# Storage.net
KiCad netlist of a schematic drawn in Altium Designer
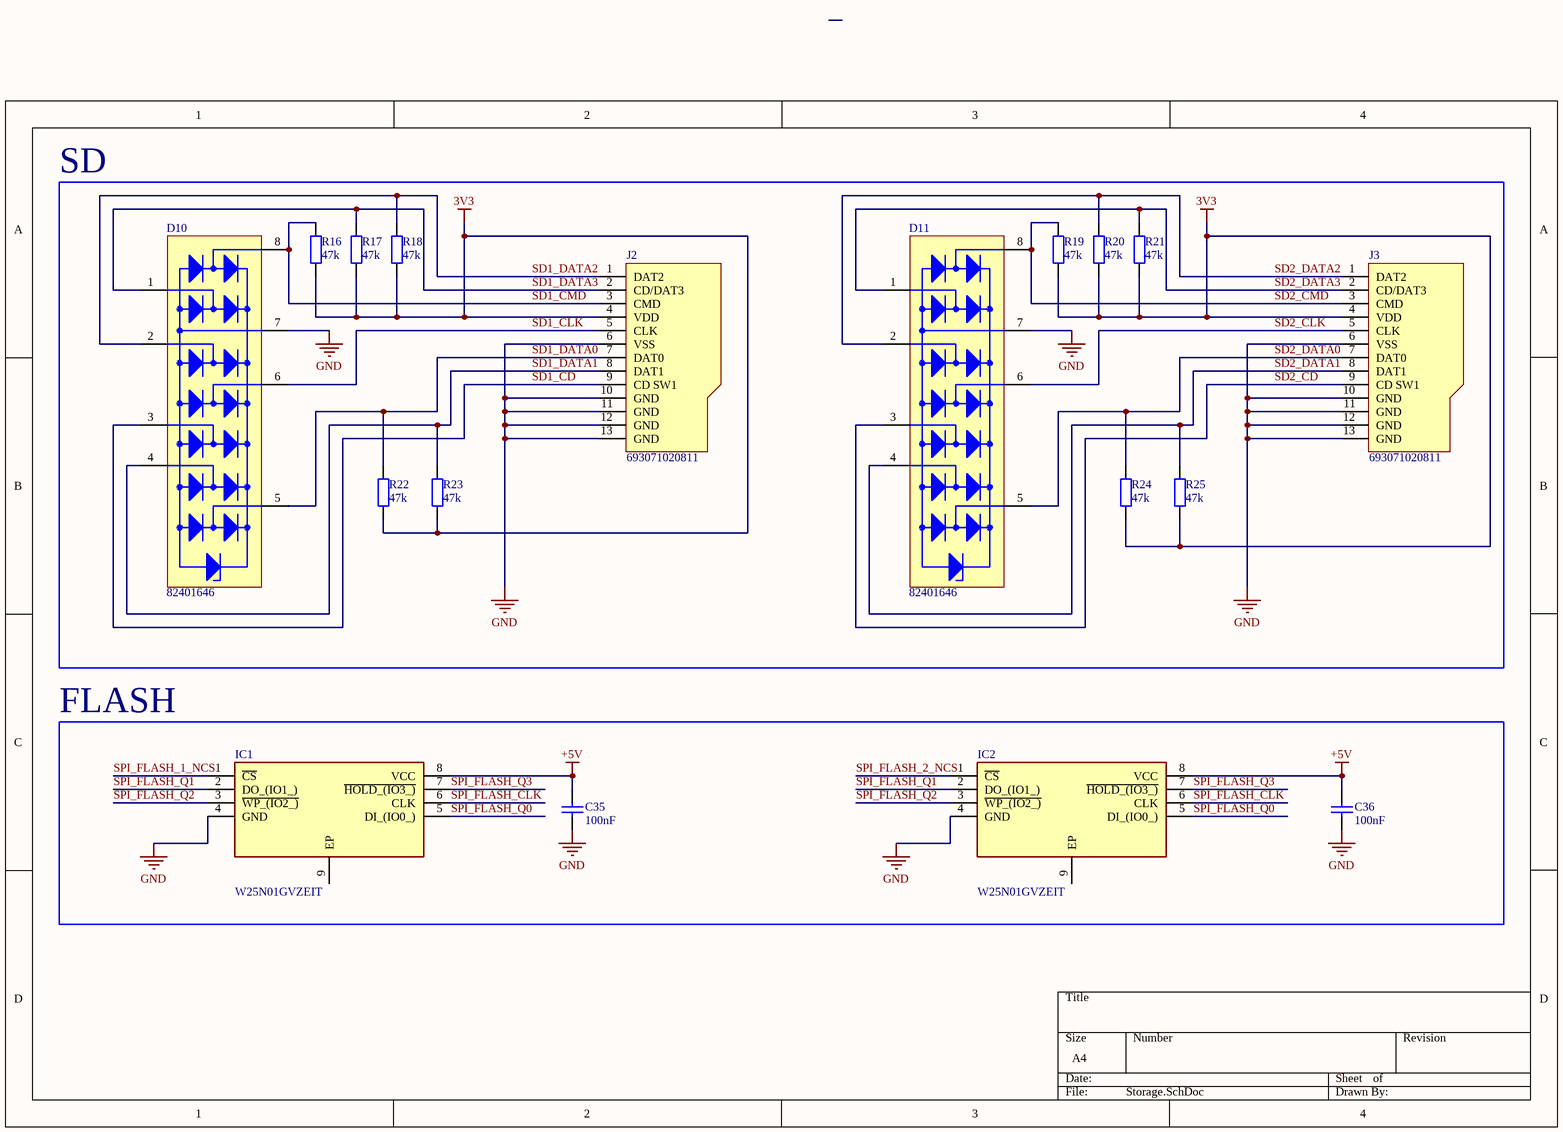
[diagram p0: Storage.SchDoc]

(export (version "E")
  (design (tool "Eeschema 10.0.6"))
  (components
    (comp (ref "C35")
      (value "100nF")
      (footprint "WCAP-CSGP_0603_L1.6W0.8H0.8_Reflow")
      (description "WCAP-CSGP Multilayer Ceramic Chip Capacitor, General Purpose, size 0603, X7R, 100nF, 25VDC")
      (fields
        (field (name "MANUFACTURER") "Wurth Elektronik")
        (field (name "MANUFACTURER PART NUMBER") "885012206071")
      )
      (libsource (lib "LEEM UPM") (part "885012209047R"))
    )
    (comp (ref "C36")
      (value "100nF")
      (footprint "WCAP-CSGP_0603_L1.6W0.8H0.8_Reflow")
      (description "WCAP-CSGP Multilayer Ceramic Chip Capacitor, General Purpose, size 0603, X7R, 100nF, 25VDC")
      (fields
        (field (name "MANUFACTURER") "Wurth Elektronik")
        (field (name "MANUFACTURER PART NUMBER") "885012206071")
      )
      (libsource (lib "LEEM UPM") (part "885012209047R"))
    )
    (comp (ref "D10")
      (value "82401646")
      (footprint "WE-TVS_MSOP-8L")
      (description "WE-TVS TVS Diode – Super Speed Series, MSOP-8L, 6+1 Channel, 5V, 0.2pF")
      (fields (field (name "MANUFACTURER") "Wurth Elektronik"))
      (libsource (lib "LEEM UPM") (part "82401646"))
    )
    (comp (ref "D11")
      (value "82401646")
      (footprint "WE-TVS_MSOP-8L")
      (description "WE-TVS TVS Diode – Super Speed Series, MSOP-8L, 6+1 Channel, 5V, 0.2pF")
      (fields (field (name "MANUFACTURER") "Wurth Elektronik"))
      (libsource (lib "LEEM UPM") (part "82401646"))
    )
    (comp (ref "IC1")
      (value "W25N01GVZEIT")
      (footprint "SamacSys:SON127P800X600X80-9N-D")
      (description "Integrated Circuit")
      (fields (field (name "MOUSER PART NUMBER") "454-W25N01GVZEIT"))
      (libsource (lib "*") (part "W25N01GVZEIT"))
    )
    (comp (ref "IC2")
      (value "W25N01GVZEIT")
      (footprint "SamacSys:SON127P800X600X80-9N-D")
      (description "Integrated Circuit")
      (fields (field (name "MOUSER PART NUMBER") "454-W25N01GVZEIT"))
      (libsource (lib "*") (part "W25N01GVZEIT"))
    )
    (comp (ref "J2")
      (value "693071020811")
      (footprint "693071020811")
      (description "WR-CRD Micro SD Card Connector Push & Push")
      (fields (field (name "MANUFACTURER") "Wurth Elektronik"))
      (libsource (lib "LEEM UPM") (part "693071020811"))
    )
    (comp (ref "J3")
      (value "693071020811")
      (footprint "693071020811")
      (description "WR-CRD Micro SD Card Connector Push & Push")
      (fields (field (name "MANUFACTURER") "Wurth Elektronik"))
      (libsource (lib "LEEM UPM") (part "693071020811"))
    )
    (comp (ref "R16")
      (value "47k")
      (footprint "WRIS-RSKS_0603_Reflow")
      (description "WRIS-RSKS Thick Film Resistor, size 0603, 47000Ohm, 100mW")
      (fields
        (field (name "MANUFACTURER") "Wurth Elektronik")
        (field (name "MANUFACTURER PART NUMBER") "560112116025")
      )
      (libsource (lib "LEEM UPM") (part "560112140010"))
    )
    (comp (ref "R17")
      (value "47k")
      (footprint "WRIS-RSKS_0603_Reflow")
      (description "WRIS-RSKS Thick Film Resistor, size 0603, 47000Ohm, 100mW")
      (fields
        (field (name "MANUFACTURER") "Wurth Elektronik")
        (field (name "MANUFACTURER PART NUMBER") "560112116025")
      )
      (libsource (lib "LEEM UPM") (part "560112140010"))
    )
    (comp (ref "R18")
      (value "47k")
      (footprint "WRIS-RSKS_0603_Reflow")
      (description "WRIS-RSKS Thick Film Resistor, size 0603, 47000Ohm, 100mW")
      (fields
        (field (name "MANUFACTURER") "Wurth Elektronik")
        (field (name "MANUFACTURER PART NUMBER") "560112116025")
      )
      (libsource (lib "LEEM UPM") (part "560112140010"))
    )
    (comp (ref "R19")
      (value "47k")
      (footprint "WRIS-RSKS_0603_Reflow")
      (description "WRIS-RSKS Thick Film Resistor, size 0603, 47000Ohm, 100mW")
      (fields
        (field (name "MANUFACTURER") "Wurth Elektronik")
        (field (name "MANUFACTURER PART NUMBER") "560112116025")
      )
      (libsource (lib "LEEM UPM") (part "560112140010"))
    )
    (comp (ref "R20")
      (value "47k")
      (footprint "WRIS-RSKS_0603_Reflow")
      (description "WRIS-RSKS Thick Film Resistor, size 0603, 47000Ohm, 100mW")
      (fields
        (field (name "MANUFACTURER") "Wurth Elektronik")
        (field (name "MANUFACTURER PART NUMBER") "560112116025")
      )
      (libsource (lib "LEEM UPM") (part "560112140010"))
    )
    (comp (ref "R21")
      (value "47k")
      (footprint "WRIS-RSKS_0603_Reflow")
      (description "WRIS-RSKS Thick Film Resistor, size 0603, 47000Ohm, 100mW")
      (fields
        (field (name "MANUFACTURER") "Wurth Elektronik")
        (field (name "MANUFACTURER PART NUMBER") "560112116025")
      )
      (libsource (lib "LEEM UPM") (part "560112140010"))
    )
    (comp (ref "R22")
      (value "47k")
      (footprint "WRIS-RSKS_0603_Reflow")
      (description "WRIS-RSKS Thick Film Resistor, size 0603, 47000Ohm, 100mW")
      (fields
        (field (name "MANUFACTURER") "Wurth Elektronik")
        (field (name "MANUFACTURER PART NUMBER") "560112116025")
      )
      (libsource (lib "LEEM UPM") (part "560112140010"))
    )
    (comp (ref "R23")
      (value "47k")
      (footprint "WRIS-RSKS_0603_Reflow")
      (description "WRIS-RSKS Thick Film Resistor, size 0603, 47000Ohm, 100mW")
      (fields
        (field (name "MANUFACTURER") "Wurth Elektronik")
        (field (name "MANUFACTURER PART NUMBER") "560112116025")
      )
      (libsource (lib "LEEM UPM") (part "560112140010"))
    )
    (comp (ref "R24")
      (value "47k")
      (footprint "WRIS-RSKS_0603_Reflow")
      (description "WRIS-RSKS Thick Film Resistor, size 0603, 47000Ohm, 100mW")
      (fields
        (field (name "MANUFACTURER") "Wurth Elektronik")
        (field (name "MANUFACTURER PART NUMBER") "560112116025")
      )
      (libsource (lib "LEEM UPM") (part "560112140010"))
    )
    (comp (ref "R25")
      (value "47k")
      (footprint "WRIS-RSKS_0603_Reflow")
      (description "WRIS-RSKS Thick Film Resistor, size 0603, 47000Ohm, 100mW")
      (fields
        (field (name "MANUFACTURER") "Wurth Elektronik")
        (field (name "MANUFACTURER PART NUMBER") "560112116025")
      )
      (libsource (lib "LEEM UPM") (part "560112140010"))
    )
  )
  (nets
    (net (code "1") (name "+5V") (class "Default")
      (node (ref "C35") (pin "2") (pinfunction "2_2") (pintype "passive"))
      (node (ref "C36") (pin "2") (pinfunction "2_2") (pintype "passive"))
      (node (ref "IC1") (pin "8") (pinfunction "VCC_8") (pintype "passive"))
      (node (ref "IC2") (pin "8") (pinfunction "VCC_8") (pintype "passive"))
    )
    (net (code "2") (name "/SD1_CD") (class "Default")
      (node (ref "D10") (pin "3") (pinfunction "I/O_3_3") (pintype "passive"))
      (node (ref "J2") (pin "9") (pinfunction "CD_SW1_9") (pintype "passive"))
    )
    (net (code "3") (name "/SD1_CLK") (class "Default")
      (node (ref "D10") (pin "6") (pinfunction "I/O_6_6") (pintype "passive"))
      (node (ref "J2") (pin "5") (pinfunction "CLK_5") (pintype "passive"))
    )
    (net (code "4") (name "/SD1_CMD") (class "Default")
      (node (ref "D10") (pin "8") (pinfunction "VDD_8") (pintype "passive"))
      (node (ref "J2") (pin "3") (pinfunction "CMD_3") (pintype "passive"))
      (node (ref "R16") (pin "2") (pinfunction "2_2") (pintype "passive"))
    )
    (net (code "5") (name "/SD1_DATA0") (class "Default")
      (node (ref "D10") (pin "5") (pinfunction "I/O_5_5") (pintype "passive"))
      (node (ref "J2") (pin "7") (pinfunction "DAT0_7") (pintype "passive"))
      (node (ref "R22") (pin "2") (pinfunction "2_2") (pintype "passive"))
    )
    (net (code "6") (name "/SD1_DATA1") (class "Default")
      (node (ref "D10") (pin "4") (pinfunction "I/O_4_4") (pintype "passive"))
      (node (ref "J2") (pin "8") (pinfunction "DAT1_8") (pintype "passive"))
      (node (ref "R23") (pin "2") (pinfunction "2_2") (pintype "passive"))
    )
    (net (code "7") (name "/SD1_DATA2") (class "Default")
      (node (ref "D10") (pin "2") (pinfunction "I/O_2_2") (pintype "passive"))
      (node (ref "J2") (pin "1") (pinfunction "DAT2_1") (pintype "passive"))
      (node (ref "R18") (pin "2") (pinfunction "2_2") (pintype "passive"))
    )
    (net (code "8") (name "/SD1_DATA3") (class "Default")
      (node (ref "D10") (pin "1") (pinfunction "I/O_1_1") (pintype "passive"))
      (node (ref "J2") (pin "2") (pinfunction "CD/DAT3_2") (pintype "passive"))
      (node (ref "R17") (pin "2") (pinfunction "2_2") (pintype "passive"))
    )
    (net (code "9") (name "/SD2_CD") (class "Default")
      (node (ref "D11") (pin "3") (pinfunction "I/O_3_3") (pintype "passive"))
      (node (ref "J3") (pin "9") (pinfunction "CD_SW1_9") (pintype "passive"))
    )
    (net (code "10") (name "/SD2_CLK") (class "Default")
      (node (ref "D11") (pin "6") (pinfunction "I/O_6_6") (pintype "passive"))
      (node (ref "J3") (pin "5") (pinfunction "CLK_5") (pintype "passive"))
    )
    (net (code "11") (name "/SD2_CMD") (class "Default")
      (node (ref "D11") (pin "8") (pinfunction "VDD_8") (pintype "passive"))
      (node (ref "J3") (pin "3") (pinfunction "CMD_3") (pintype "passive"))
      (node (ref "R19") (pin "2") (pinfunction "2_2") (pintype "passive"))
    )
    (net (code "12") (name "/SD2_DATA0") (class "Default")
      (node (ref "D11") (pin "5") (pinfunction "I/O_5_5") (pintype "passive"))
      (node (ref "J3") (pin "7") (pinfunction "DAT0_7") (pintype "passive"))
      (node (ref "R24") (pin "2") (pinfunction "2_2") (pintype "passive"))
    )
    (net (code "13") (name "/SD2_DATA1") (class "Default")
      (node (ref "D11") (pin "4") (pinfunction "I/O_4_4") (pintype "passive"))
      (node (ref "J3") (pin "8") (pinfunction "DAT1_8") (pintype "passive"))
      (node (ref "R25") (pin "2") (pinfunction "2_2") (pintype "passive"))
    )
    (net (code "14") (name "/SD2_DATA2") (class "Default")
      (node (ref "D11") (pin "2") (pinfunction "I/O_2_2") (pintype "passive"))
      (node (ref "J3") (pin "1") (pinfunction "DAT2_1") (pintype "passive"))
      (node (ref "R20") (pin "2") (pinfunction "2_2") (pintype "passive"))
    )
    (net (code "15") (name "/SD2_DATA3") (class "Default")
      (node (ref "D11") (pin "1") (pinfunction "I/O_1_1") (pintype "passive"))
      (node (ref "J3") (pin "2") (pinfunction "CD/DAT3_2") (pintype "passive"))
      (node (ref "R21") (pin "2") (pinfunction "2_2") (pintype "passive"))
    )
    (net (code "16") (name "/SPI_FLASH_1_NCS") (class "Default")
      (node (ref "IC1") (pin "1") (pinfunction "~{CS}_1") (pintype "passive"))
    )
    (net (code "17") (name "/SPI_FLASH_2_NCS") (class "Default")
      (node (ref "IC2") (pin "1") (pinfunction "~{CS}_1") (pintype "passive"))
    )
    (net (code "18") (name "/SPI_FLASH_CLK") (class "Default")
      (node (ref "IC1") (pin "6") (pinfunction "CLK_6") (pintype "passive"))
      (node (ref "IC2") (pin "6") (pinfunction "CLK_6") (pintype "passive"))
    )
    (net (code "19") (name "/SPI_FLASH_Q0") (class "Default")
      (node (ref "IC1") (pin "5") (pinfunction "DI_(IO0_)_5") (pintype "passive"))
      (node (ref "IC2") (pin "5") (pinfunction "DI_(IO0_)_5") (pintype "passive"))
    )
    (net (code "20") (name "/SPI_FLASH_Q1") (class "Default")
      (node (ref "IC1") (pin "2") (pinfunction "DO_(IO1_)_2") (pintype "passive"))
      (node (ref "IC2") (pin "2") (pinfunction "DO_(IO1_)_2") (pintype "passive"))
    )
    (net (code "21") (name "/SPI_FLASH_Q2") (class "Default")
      (node (ref "IC1") (pin "3") (pinfunction "~{WP_(IO2_)}_3") (pintype "passive"))
      (node (ref "IC2") (pin "3") (pinfunction "~{WP_(IO2_)}_3") (pintype "passive"))
    )
    (net (code "22") (name "/SPI_FLASH_Q3") (class "Default")
      (node (ref "IC1") (pin "7") (pinfunction "~{HOLD_(IO3_)}_7") (pintype "passive"))
      (node (ref "IC2") (pin "7") (pinfunction "~{HOLD_(IO3_)}_7") (pintype "passive"))
    )
    (net (code "23") (name "3V3") (class "Default")
      (node (ref "J2") (pin "4") (pinfunction "VDD_4") (pintype "passive"))
      (node (ref "J3") (pin "4") (pinfunction "VDD_4") (pintype "passive"))
      (node (ref "R16") (pin "1") (pinfunction "1_1") (pintype "passive"))
      (node (ref "R17") (pin "1") (pinfunction "1_1") (pintype "passive"))
      (node (ref "R18") (pin "1") (pinfunction "1_1") (pintype "passive"))
      (node (ref "R19") (pin "1") (pinfunction "1_1") (pintype "passive"))
      (node (ref "R20") (pin "1") (pinfunction "1_1") (pintype "passive"))
      (node (ref "R21") (pin "1") (pinfunction "1_1") (pintype "passive"))
      (node (ref "R22") (pin "1") (pinfunction "1_1") (pintype "passive"))
      (node (ref "R23") (pin "1") (pinfunction "1_1") (pintype "passive"))
      (node (ref "R24") (pin "1") (pinfunction "1_1") (pintype "passive"))
      (node (ref "R25") (pin "1") (pinfunction "1_1") (pintype "passive"))
    )
    (net (code "24") (name "GND") (class "Default")
      (node (ref "C35") (pin "1") (pinfunction "1_1") (pintype "passive"))
      (node (ref "C36") (pin "1") (pinfunction "1_1") (pintype "passive"))
      (node (ref "D10") (pin "7") (pinfunction "GND_7") (pintype "passive"))
      (node (ref "D11") (pin "7") (pinfunction "GND_7") (pintype "passive"))
      (node (ref "IC1") (pin "4") (pinfunction "GND_4") (pintype "passive"))
      (node (ref "IC2") (pin "4") (pinfunction "GND_4") (pintype "passive"))
      (node (ref "J2") (pin "10") (pinfunction "GND_10") (pintype "passive"))
      (node (ref "J2") (pin "11") (pinfunction "GND_11") (pintype "passive"))
      (node (ref "J2") (pin "12") (pinfunction "GND_12") (pintype "passive"))
      (node (ref "J2") (pin "13") (pinfunction "GND_13") (pintype "passive"))
      (node (ref "J2") (pin "6") (pinfunction "VSS_6") (pintype "passive"))
      (node (ref "J3") (pin "10") (pinfunction "GND_10") (pintype "passive"))
      (node (ref "J3") (pin "11") (pinfunction "GND_11") (pintype "passive"))
      (node (ref "J3") (pin "12") (pinfunction "GND_12") (pintype "passive"))
      (node (ref "J3") (pin "13") (pinfunction "GND_13") (pintype "passive"))
      (node (ref "J3") (pin "6") (pinfunction "VSS_6") (pintype "passive"))
    )
    (net (code "25") (name "unconnected-(IC1-EP-Pad9)") (class "Default")
      (node (ref "IC1") (pin "9") (pinfunction "EP_9") (pintype "passive"))
    )
    (net (code "26") (name "unconnected-(IC2-EP-Pad9)") (class "Default")
      (node (ref "IC2") (pin "9") (pinfunction "EP_9") (pintype "passive"))
    )
  )
)
